# RoomModule.net
KiCad netlist of a schematic drawn in Altium Designer
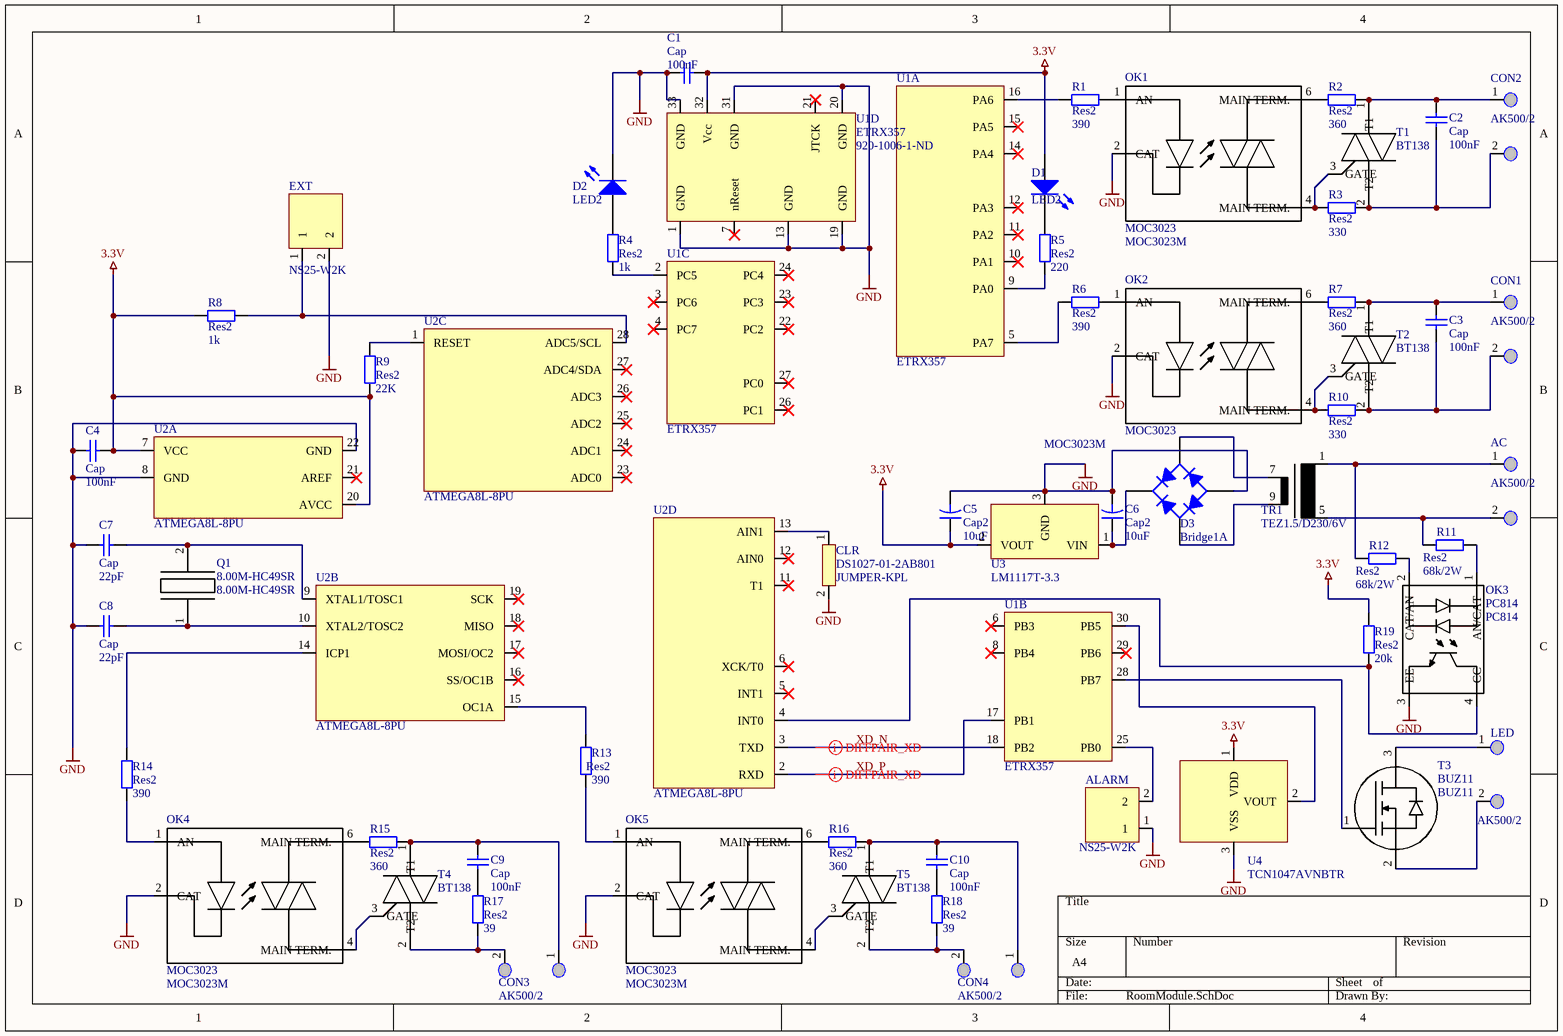
[diagram p0: RoomModule.SchDoc]

(export (version "E")
  (design (tool "Eeschema 10.0.6"))
  (components
    (comp (ref "AC")
      (value "AK500/2")
      (footprint "AK500/2")
      (description "AK500/2 connector")
      (libsource (lib "pads15l_schematic") (part "AK500/2"))
    )
    (comp (ref "ALARM")
      (value "NS25-W2K")
      (footprint "NS25-W2K")
      (description "2-pin Right Angle PCB Connector")
      (libsource (lib "pads15l_schematic") (part "NS25-W2K"))
    )
    (comp (ref "C1")
      (value "Cap")
      (footprint "RAD-0.3")
      (description "Capacitor")
      (fields (field (name "ALTIUM_VALUE") "100nF") (field (name "PUBLISHER") "Altium Limited"))
      (libsource (lib "Miscellaneous Devices") (part "Cap"))
    )
    (comp (ref "C2")
      (value "Cap")
      (footprint "RAD-0.3")
      (description "Capacitor")
      (fields (field (name "ALTIUM_VALUE") "100nF") (field (name "PUBLISHER") "Altium Limited"))
      (libsource (lib "Miscellaneous Devices") (part "Cap"))
    )
    (comp (ref "C3")
      (value "Cap")
      (footprint "RAD-0.3")
      (description "Capacitor")
      (fields (field (name "ALTIUM_VALUE") "100nF") (field (name "PUBLISHER") "Altium Limited"))
      (libsource (lib "Miscellaneous Devices") (part "Cap"))
    )
    (comp (ref "C4")
      (value "Cap")
      (footprint "RAD-0.3")
      (description "Capacitor")
      (fields (field (name "ALTIUM_VALUE") "100nF") (field (name "PUBLISHER") "Altium Limited"))
      (libsource (lib "Miscellaneous Devices") (part "Cap"))
    )
    (comp (ref "C5")
      (value "Cap2")
      (footprint "CAPR5-4X5")
      (description "Capacitor")
      (fields (field (name "ALTIUM_VALUE") "10uF") (field (name "PUBLISHER") "Altium Limited"))
      (libsource (lib "Miscellaneous Devices") (part "Cap2"))
    )
    (comp (ref "C6")
      (value "Cap2")
      (footprint "CAPR5-4X5")
      (description "Capacitor")
      (fields (field (name "ALTIUM_VALUE") "10uF") (field (name "PUBLISHER") "Altium Limited"))
      (libsource (lib "Miscellaneous Devices") (part "Cap2"))
    )
    (comp (ref "C7")
      (value "Cap")
      (footprint "RAD-0.3")
      (description "Capacitor")
      (fields (field (name "ALTIUM_VALUE") "22pF") (field (name "PUBLISHER") "Altium Limited"))
      (libsource (lib "Miscellaneous Devices") (part "Cap"))
    )
    (comp (ref "C8")
      (value "Cap")
      (footprint "RAD-0.3")
      (description "Capacitor")
      (fields (field (name "ALTIUM_VALUE") "22pF") (field (name "PUBLISHER") "Altium Limited"))
      (libsource (lib "Miscellaneous Devices") (part "Cap"))
    )
    (comp (ref "C9")
      (value "Cap")
      (footprint "RAD-0.3")
      (description "Capacitor")
      (fields (field (name "ALTIUM_VALUE") "100nF") (field (name "PUBLISHER") "Altium Limited"))
      (libsource (lib "Miscellaneous Devices") (part "Cap"))
    )
    (comp (ref "C10")
      (value "Cap")
      (footprint "RAD-0.3")
      (description "Capacitor")
      (fields (field (name "ALTIUM_VALUE") "100nF") (field (name "PUBLISHER") "Altium Limited"))
      (libsource (lib "Miscellaneous Devices") (part "Cap"))
    )
    (comp (ref "CLR")
      (value "DS1027-01-2AB801")
      (footprint "DS1027-01")
      (description "2.54 mm jumper")
      (fields (field (name "SUPPLIER PART NUMBER 1") "JUMPER-KPL"))
      (libsource (lib "pads15l_schematic") (part "DS1027-01-2AB801"))
    )
    (comp (ref "CON1")
      (value "AK500/2")
      (footprint "AK500/2")
      (description "AK500/2 connector")
      (libsource (lib "pads15l_schematic") (part "AK500/2"))
    )
    (comp (ref "CON2")
      (value "AK500/2")
      (footprint "AK500/2")
      (description "AK500/2 connector")
      (libsource (lib "pads15l_schematic") (part "AK500/2"))
    )
    (comp (ref "CON3")
      (value "AK500/2")
      (footprint "AK500/2")
      (description "AK500/2 connector")
      (libsource (lib "pads15l_schematic") (part "AK500/2"))
    )
    (comp (ref "CON4")
      (value "AK500/2")
      (footprint "AK500/2")
      (description "AK500/2 connector")
      (libsource (lib "pads15l_schematic") (part "AK500/2"))
    )
    (comp (ref "D1")
      (value "LED2")
      (footprint "3.2X1.6X1.1")
      (description "Typical RED, GREEN, YELLOW, AMBER GaAs LED")
      (fields (field (name "PUBLISHER") "Altium Limited"))
      (libsource (lib "Miscellaneous Devices") (part "LED2"))
    )
    (comp (ref "D2")
      (value "LED2")
      (footprint "3.2X1.6X1.1")
      (description "Typical RED, GREEN, YELLOW, AMBER GaAs LED")
      (fields (field (name "PUBLISHER") "Altium Limited"))
      (libsource (lib "Miscellaneous Devices") (part "LED2"))
    )
    (comp (ref "D3")
      (value "Bridge1A")
      (footprint "D-38")
      (description "Full Wave Diode Bridge")
      (fields (field (name "PUBLISHER") "Altium Limited"))
      (libsource (lib "Miscellaneous Devices") (part "Bridge1"))
    )
    (comp (ref "EXT")
      (value "NS25-W2K")
      (footprint "NS25-W2K")
      (description "2-pin Right Angle PCB Connector")
      (libsource (lib "") (part "NS25-W2K_1"))
    )
    (comp (ref "LED")
      (value "AK500/2")
      (footprint "AK500/2")
      (description "AK500/2 connector")
      (libsource (lib "pads15l_schematic") (part "AK500/2"))
    )
    (comp (ref "OK1")
      (value "MOC3023")
      (footprint "DIP6")
      (description "6-Pin DIP Random-Phase Optoisolators Triac Driver Output")
      (fields (field (name "SUPPLIER PART NUMBER 1") "MOC3023M"))
      (libsource (lib "pads15l_schematic") (part "MOC3023"))
    )
    (comp (ref "OK2")
      (value "MOC3023")
      (footprint "DIP6")
      (description "6-Pin DIP Random-Phase Optoisolators Triac Driver Output")
      (fields (field (name "SUPPLIER PART NUMBER 1") "MOC3023M"))
      (libsource (lib "pads15l_schematic") (part "MOC3023"))
    )
    (comp (ref "OK3")
      (value "PC814")
      (footprint "DIP4")
      (description "4 pin DIP phototransistor photocoupler")
      (fields (field (name "SUPPLIER PART NUMBER 1") "PC814"))
      (libsource (lib "pads15l_schematic") (part "PC814"))
    )
    (comp (ref "OK4")
      (value "MOC3023")
      (footprint "DIP6")
      (description "6-Pin DIP Random-Phase Optoisolators Triac Driver Output")
      (fields (field (name "SUPPLIER PART NUMBER 1") "MOC3023M"))
      (libsource (lib "pads15l_schematic") (part "MOC3023"))
    )
    (comp (ref "OK5")
      (value "MOC3023")
      (footprint "DIP6")
      (description "6-Pin DIP Random-Phase Optoisolators Triac Driver Output")
      (fields (field (name "SUPPLIER PART NUMBER 1") "MOC3023M"))
      (libsource (lib "pads15l_schematic") (part "MOC3023"))
    )
    (comp (ref "Q1")
      (value "8.00M-HC49SR")
      (footprint "HC49-S")
      (description "HC49SR 8 MHz crystal")
      (fields (field (name "SUPPLIER PART NUMBER 1") "8.00M-HC49SR"))
      (libsource (lib "pads15l_schematic") (part "8.00M-HC49SR"))
    )
    (comp (ref "R1")
      (value "Res2")
      (footprint "AXIAL-0.4")
      (description "Resistor")
      (fields (field (name "ALTIUM_VALUE") "390") (field (name "PUBLISHER") "Altium Limited"))
      (libsource (lib "") (part "Res2_1"))
    )
    (comp (ref "R2")
      (value "Res2")
      (footprint "AXIAL-0.4")
      (description "Resistor")
      (fields (field (name "ALTIUM_VALUE") "360") (field (name "PUBLISHER") "Altium Limited"))
      (libsource (lib "") (part "Res2_1"))
    )
    (comp (ref "R3")
      (value "Res2")
      (footprint "AXIAL-0.4")
      (description "Resistor")
      (fields (field (name "ALTIUM_VALUE") "330") (field (name "PUBLISHER") "Altium Limited"))
      (libsource (lib "") (part "Res2_1"))
    )
    (comp (ref "R4")
      (value "Res2")
      (footprint "AXIAL-0.4")
      (description "Resistor")
      (fields (field (name "ALTIUM_VALUE") "1k") (field (name "PUBLISHER") "Altium Limited"))
      (libsource (lib "") (part "Res2_3"))
    )
    (comp (ref "R5")
      (value "Res2")
      (footprint "AXIAL-0.4")
      (description "Resistor")
      (fields (field (name "ALTIUM_VALUE") "220") (field (name "PUBLISHER") "Altium Limited"))
      (libsource (lib "") (part "Res2_3"))
    )
    (comp (ref "R6")
      (value "Res2")
      (footprint "AXIAL-0.4")
      (description "Resistor")
      (fields (field (name "ALTIUM_VALUE") "390") (field (name "PUBLISHER") "Altium Limited"))
      (libsource (lib "") (part "Res2_1"))
    )
    (comp (ref "R7")
      (value "Res2")
      (footprint "AXIAL-0.4")
      (description "Resistor")
      (fields (field (name "ALTIUM_VALUE") "360") (field (name "PUBLISHER") "Altium Limited"))
      (libsource (lib "") (part "Res2_1"))
    )
    (comp (ref "R8")
      (value "Res2")
      (footprint "AXIAL-0.4")
      (description "Resistor")
      (fields (field (name "ALTIUM_VALUE") "1k") (field (name "PUBLISHER") "Altium Limited"))
      (libsource (lib "") (part "Res2_2"))
    )
    (comp (ref "R9")
      (value "Res2")
      (footprint "AXIAL-0.4")
      (description "Resistor")
      (fields (field (name "ALTIUM_VALUE") "22K") (field (name "PUBLISHER") "Altium Limited"))
      (libsource (lib "Miscellaneous Devices") (part "Res2"))
    )
    (comp (ref "R10")
      (value "Res2")
      (footprint "AXIAL-0.4")
      (description "Resistor")
      (fields (field (name "ALTIUM_VALUE") "330") (field (name "PUBLISHER") "Altium Limited"))
      (libsource (lib "") (part "Res2_1"))
    )
    (comp (ref "R11")
      (value "Res2")
      (footprint "AXIAL-0.4")
      (description "Resistor")
      (fields (field (name "ALTIUM_VALUE") "68k/2W") (field (name "PUBLISHER") "Altium Limited"))
      (libsource (lib "") (part "Res2_2"))
    )
    (comp (ref "R12")
      (value "Res2")
      (footprint "AXIAL-0.4")
      (description "Resistor")
      (fields (field (name "ALTIUM_VALUE") "68k/2W") (field (name "PUBLISHER") "Altium Limited"))
      (libsource (lib "") (part "Res2_2"))
    )
    (comp (ref "R13")
      (value "Res2")
      (footprint "AXIAL-0.4")
      (description "Resistor")
      (fields (field (name "ALTIUM_VALUE") "390") (field (name "PUBLISHER") "Altium Limited"))
      (libsource (lib "") (part "Res2_3"))
    )
    (comp (ref "R14")
      (value "Res2")
      (footprint "AXIAL-0.4")
      (description "Resistor")
      (fields (field (name "ALTIUM_VALUE") "390") (field (name "PUBLISHER") "Altium Limited"))
      (libsource (lib "") (part "Res2_3"))
    )
    (comp (ref "R15")
      (value "Res2")
      (footprint "AXIAL-0.4")
      (description "Resistor")
      (fields (field (name "ALTIUM_VALUE") "360") (field (name "PUBLISHER") "Altium Limited"))
      (libsource (lib "") (part "Res2_1"))
    )
    (comp (ref "R16")
      (value "Res2")
      (footprint "AXIAL-0.4")
      (description "Resistor")
      (fields (field (name "ALTIUM_VALUE") "360") (field (name "PUBLISHER") "Altium Limited"))
      (libsource (lib "") (part "Res2_1"))
    )
    (comp (ref "R17")
      (value "Res2")
      (footprint "AXIAL-0.4")
      (description "Resistor")
      (fields (field (name "ALTIUM_VALUE") "39") (field (name "PUBLISHER") "Altium Limited"))
      (libsource (lib "") (part "Res2_3"))
    )
    (comp (ref "R18")
      (value "Res2")
      (footprint "AXIAL-0.4")
      (description "Resistor")
      (fields (field (name "ALTIUM_VALUE") "39") (field (name "PUBLISHER") "Altium Limited"))
      (libsource (lib "") (part "Res2_3"))
    )
    (comp (ref "R19")
      (value "Res2")
      (footprint "AXIAL-0.4")
      (description "Resistor")
      (fields (field (name "ALTIUM_VALUE") "20k") (field (name "PUBLISHER") "Altium Limited"))
      (libsource (lib "") (part "Res2_3"))
    )
    (comp (ref "T1")
      (value "BT138")
      (footprint "TO220AB")
      (libsource (lib "pads15l_schematic") (part "BT138"))
    )
    (comp (ref "T2")
      (value "BT138")
      (footprint "TO220AB")
      (libsource (lib "pads15l_schematic") (part "BT138"))
    )
    (comp (ref "T3")
      (value "BUZ11")
      (footprint "TO220AB")
      (description "N-Channel Power MOSFET 50V, 30A, 40mOhm")
      (fields (field (name "SUPPLIER PART NUMBER 1") "BUZ11"))
      (libsource (lib "pads15l_schematic") (part "BUZ11"))
    )
    (comp (ref "T4")
      (value "BT138")
      (footprint "TO220AB")
      (libsource (lib "pads15l_schematic") (part "BT138"))
    )
    (comp (ref "T5")
      (value "BT138")
      (footprint "TO220AB")
      (libsource (lib "pads15l_schematic") (part "BT138"))
    )
    (comp (ref "TR1")
      (value "TEZ1.5/D230/6V")
      (footprint "TEZ1.5")
      (description "Transformer for PCB")
      (libsource (lib "pads15l_schematic") (part "TEZ1.5/D230/6V"))
    )
    (comp (ref "U1")
      (value "ETRX357")
      (footprint "ETRX3")
      (description "Low power 2.4GHz ZigBee module, based on the latest Ember EM357 single chip ZigBeeTM solution")
      (fields (field (name "SUPPLIER PART NUMBER 1") "920-1006-1-ND"))
      (libsource (lib "") (part "ETRX357_2"))
    )
    (comp (ref "U2")
      (value "ATMEGA8L-8PU")
      (footprint "DIP28_600")
      (description "8-bit AVR with 8K Bytes In-System Programmable Flash")
      (libsource (lib "pads15l_schematic") (part "ATMEGA8L-8PU"))
    )
    (comp (ref "U3")
      (value "LM1117T-3.3")
      (footprint "TO252")
      (description "LDO voltage regulator with 800mA output current and 3.3V fixed voltage")
      (libsource (lib "pads15l_schematic") (part "LM1117DT-3.3"))
    )
    (comp (ref "U4")
      (value "TCN1047AVNBTR")
      (footprint "SOT23B")
      (description "Precision Temperature-to-Voltage Converter")
      (libsource (lib "pads15l_schematic") (part "TC1047AVNBTR"))
    )
  )
  (nets
    (net (code "1") (name "/XD_N") (class "Default")
      (node (ref "U1") (pin "18") (pinfunction "PB2_18") (pintype "passive"))
      (node (ref "U2") (pin "3") (pinfunction "TXD_3") (pintype "passive"))
    )
    (net (code "2") (name "/XD_P") (class "Default")
      (node (ref "U1") (pin "17") (pinfunction "PB1_17") (pintype "passive"))
      (node (ref "U2") (pin "2") (pinfunction "RXD_2") (pintype "passive"))
    )
    (net (code "3") (name "3.3V") (class "Default")
      (node (ref "C1") (pin "2") (pinfunction "2_2") (pintype "passive"))
      (node (ref "C4") (pin "2") (pinfunction "2_2") (pintype "passive"))
      (node (ref "C5") (pin "1") (pinfunction "1_1") (pintype "passive"))
      (node (ref "D1") (pin "1") (pinfunction "A_1") (pintype "passive"))
      (node (ref "R19") (pin "1") (pinfunction "1_1") (pintype "passive"))
      (node (ref "R8") (pin "2") (pinfunction "2_2") (pintype "passive"))
      (node (ref "R9") (pin "1") (pinfunction "1_1") (pintype "passive"))
      (node (ref "U1") (pin "32") (pinfunction "Vcc_32") (pintype "passive"))
      (node (ref "U2") (pin "20") (pinfunction "AVCC_20") (pintype "passive"))
      (node (ref "U2") (pin "7") (pinfunction "VCC_7") (pintype "passive"))
      (node (ref "U3") (pin "2") (pinfunction "VOUT_2") (pintype "passive"))
      (node (ref "U4") (pin "1") (pinfunction "VDD_1") (pintype "passive"))
    )
    (net (code "4") (name "GND") (class "Default")
      (node (ref "ALARM") (pin "1") (pinfunction "1_1") (pintype "passive"))
      (node (ref "C1") (pin "1") (pinfunction "1_1") (pintype "passive"))
      (node (ref "C4") (pin "1") (pinfunction "1_1") (pintype "passive"))
      (node (ref "C5") (pin "2") (pinfunction "2_2") (pintype "passive"))
      (node (ref "C6") (pin "2") (pinfunction "2_2") (pintype "passive"))
      (node (ref "C7") (pin "1") (pinfunction "1_1") (pintype "passive"))
      (node (ref "C8") (pin "1") (pinfunction "1_1") (pintype "passive"))
      (node (ref "CLR") (pin "2") (pintype "passive"))
      (node (ref "D2") (pin "2") (pinfunction "K_2") (pintype "passive"))
      (node (ref "D3") (pin "3") (pinfunction "A_3") (pintype "passive"))
      (node (ref "EXT") (pin "2") (pinfunction "2_2") (pintype "passive"))
      (node (ref "OK1") (pin "2") (pinfunction "CAT_2") (pintype "passive"))
      (node (ref "OK2") (pin "2") (pinfunction "CAT_2") (pintype "passive"))
      (node (ref "OK3") (pin "3") (pinfunction "EE_3") (pintype "passive"))
      (node (ref "OK4") (pin "2") (pinfunction "CAT_2") (pintype "passive"))
      (node (ref "OK5") (pin "2") (pinfunction "CAT_2") (pintype "passive"))
      (node (ref "U1") (pin "1") (pinfunction "GND_1") (pintype "passive"))
      (node (ref "U1") (pin "13") (pinfunction "GND_13") (pintype "passive"))
      (node (ref "U1") (pin "19") (pinfunction "GND_19") (pintype "passive"))
      (node (ref "U1") (pin "20") (pinfunction "GND_20") (pintype "passive"))
      (node (ref "U1") (pin "31") (pinfunction "GND_31") (pintype "passive"))
      (node (ref "U1") (pin "33") (pinfunction "GND_33") (pintype "passive"))
      (node (ref "U2") (pin "22") (pinfunction "GND_22") (pintype "passive"))
      (node (ref "U2") (pin "8") (pinfunction "GND_8") (pintype "passive"))
      (node (ref "U3") (pin "3") (pinfunction "GND_3") (pintype "passive"))
      (node (ref "U4") (pin "3") (pinfunction "VSS_3") (pintype "passive"))
    )
    (net (code "5") (name "Net-(AC-Pad1)") (class "Default")
      (node (ref "AC") (pin "1") (pintype "passive"))
      (node (ref "R12") (pin "2") (pinfunction "2_2") (pintype "passive"))
      (node (ref "TR1") (pin "1") (pintype "passive"))
    )
    (net (code "6") (name "Net-(AC-Pad2)") (class "Default")
      (node (ref "AC") (pin "2") (pintype "passive"))
      (node (ref "R11") (pin "2") (pinfunction "2_2") (pintype "passive"))
      (node (ref "TR1") (pin "5") (pintype "passive"))
    )
    (net (code "7") (name "Net-(C9-Pad1)") (class "Default")
      (node (ref "C9") (pin "1") (pinfunction "1_1") (pintype "passive"))
      (node (ref "R17") (pin "1") (pinfunction "1_1") (pintype "passive"))
    )
    (net (code "8") (name "Net-(C10-Pad1)") (class "Default")
      (node (ref "C10") (pin "1") (pinfunction "1_1") (pintype "passive"))
      (node (ref "R18") (pin "1") (pinfunction "1_1") (pintype "passive"))
    )
    (net (code "9") (name "Net-(D1-K)") (class "Default")
      (node (ref "D1") (pin "2") (pinfunction "K_2") (pintype "passive"))
      (node (ref "R5") (pin "1") (pinfunction "1_1") (pintype "passive"))
    )
    (net (code "10") (name "Net-(D2-A)") (class "Default")
      (node (ref "D2") (pin "1") (pinfunction "A_1") (pintype "passive"))
      (node (ref "R4") (pin "1") (pinfunction "1_1") (pintype "passive"))
    )
    (net (code "11") (name "Net-(D3-C-Pad2)") (class "Default")
      (node (ref "D3") (pin "2") (pinfunction "C_2") (pintype "passive"))
      (node (ref "TR1") (pin "7") (pintype "passive"))
    )
    (net (code "12") (name "Net-(D3-C-Pad4)") (class "Default")
      (node (ref "D3") (pin "4") (pinfunction "C_4") (pintype "passive"))
      (node (ref "TR1") (pin "9") (pintype "passive"))
    )
    (net (code "13") (name "Net-(D3-K)") (class "Default")
      (node (ref "C6") (pin "1") (pinfunction "1_1") (pintype "passive"))
      (node (ref "D3") (pin "1") (pinfunction "K_1") (pintype "passive"))
      (node (ref "U3") (pin "1") (pinfunction "VIN_1") (pintype "passive"))
    )
    (net (code "14") (name "Net-(LED-Pad1)") (class "Default")
      (node (ref "LED") (pin "1") (pintype "passive"))
      (node (ref "T3") (pin "3") (pintype "passive"))
    )
    (net (code "15") (name "Net-(LED-Pad2)") (class "Default")
      (node (ref "LED") (pin "2") (pintype "passive"))
      (node (ref "T3") (pin "2") (pintype "passive"))
    )
    (net (code "16") (name "Net-(OK1-AN)") (class "Default")
      (node (ref "OK1") (pin "1") (pinfunction "AN_1") (pintype "passive"))
      (node (ref "R1") (pin "2") (pinfunction "2_2") (pintype "passive"))
    )
    (net (code "17") (name "Net-(OK1-MAIN_TERM.-Pad6)") (class "Default")
      (node (ref "OK1") (pin "6") (pinfunction "MAIN_TERM._6") (pintype "passive"))
      (node (ref "R2") (pin "1") (pinfunction "1_1") (pintype "passive"))
    )
    (net (code "18") (name "Net-(OK2-AN)") (class "Default")
      (node (ref "OK2") (pin "1") (pinfunction "AN_1") (pintype "passive"))
      (node (ref "R6") (pin "2") (pinfunction "2_2") (pintype "passive"))
    )
    (net (code "19") (name "Net-(OK2-MAIN_TERM.-Pad6)") (class "Default")
      (node (ref "OK2") (pin "6") (pinfunction "MAIN_TERM._6") (pintype "passive"))
      (node (ref "R7") (pin "1") (pinfunction "1_1") (pintype "passive"))
    )
    (net (code "20") (name "Net-(OK3-AN{slash}CAT)") (class "Default")
      (node (ref "OK3") (pin "1") (pinfunction "AN/CAT_1") (pintype "passive"))
      (node (ref "R11") (pin "1") (pinfunction "1_1") (pintype "passive"))
    )
    (net (code "21") (name "Net-(OK3-CAT{slash}AN)") (class "Default")
      (node (ref "OK3") (pin "2") (pinfunction "CAT/AN_2") (pintype "passive"))
      (node (ref "R12") (pin "1") (pinfunction "1_1") (pintype "passive"))
    )
    (net (code "22") (name "Net-(OK3-CC)") (class "Default")
      (node (ref "OK3") (pin "4") (pinfunction "CC_4") (pintype "passive"))
      (node (ref "R19") (pin "2") (pinfunction "2_2") (pintype "passive"))
      (node (ref "U2") (pin "4") (pinfunction "INT0_4") (pintype "passive"))
    )
    (net (code "23") (name "Net-(OK4-AN)") (class "Default")
      (node (ref "OK4") (pin "1") (pinfunction "AN_1") (pintype "passive"))
      (node (ref "R14") (pin "2") (pinfunction "2_2") (pintype "passive"))
    )
    (net (code "24") (name "Net-(OK4-MAIN_TERM.-Pad6)") (class "Default")
      (node (ref "OK4") (pin "6") (pinfunction "MAIN_TERM._6") (pintype "passive"))
      (node (ref "R15") (pin "1") (pinfunction "1_1") (pintype "passive"))
    )
    (net (code "25") (name "Net-(OK5-AN)") (class "Default")
      (node (ref "OK5") (pin "1") (pinfunction "AN_1") (pintype "passive"))
      (node (ref "R13") (pin "2") (pinfunction "2_2") (pintype "passive"))
    )
    (net (code "26") (name "Net-(OK5-MAIN_TERM.-Pad6)") (class "Default")
      (node (ref "OK5") (pin "6") (pinfunction "MAIN_TERM._6") (pintype "passive"))
      (node (ref "R16") (pin "1") (pinfunction "1_1") (pintype "passive"))
    )
    (net (code "27") (name "Net-(T1-GATE)") (class "Default")
      (node (ref "OK1") (pin "4") (pinfunction "MAIN_TERM._4") (pintype "passive"))
      (node (ref "R3") (pin "1") (pinfunction "1_1") (pintype "passive"))
      (node (ref "T1") (pin "3") (pinfunction "GATE_3") (pintype "passive"))
    )
    (net (code "28") (name "Net-(T1-T1)") (class "Default")
      (node (ref "C2") (pin "2") (pinfunction "2_2") (pintype "passive"))
      (node (ref "CON2") (pin "1") (pintype "passive"))
      (node (ref "R2") (pin "2") (pinfunction "2_2") (pintype "passive"))
      (node (ref "T1") (pin "1") (pinfunction "T1_1") (pintype "passive"))
    )
    (net (code "29") (name "Net-(T1-T2)") (class "Default")
      (node (ref "C2") (pin "1") (pinfunction "1_1") (pintype "passive"))
      (node (ref "CON2") (pin "2") (pintype "passive"))
      (node (ref "R3") (pin "2") (pinfunction "2_2") (pintype "passive"))
      (node (ref "T1") (pin "2") (pinfunction "T2_2") (pintype "passive"))
    )
    (net (code "30") (name "Net-(T2-GATE)") (class "Default")
      (node (ref "OK2") (pin "4") (pinfunction "MAIN_TERM._4") (pintype "passive"))
      (node (ref "R10") (pin "1") (pinfunction "1_1") (pintype "passive"))
      (node (ref "T2") (pin "3") (pinfunction "GATE_3") (pintype "passive"))
    )
    (net (code "31") (name "Net-(T2-T1)") (class "Default")
      (node (ref "C3") (pin "2") (pinfunction "2_2") (pintype "passive"))
      (node (ref "CON1") (pin "1") (pintype "passive"))
      (node (ref "R7") (pin "2") (pinfunction "2_2") (pintype "passive"))
      (node (ref "T2") (pin "1") (pinfunction "T1_1") (pintype "passive"))
    )
    (net (code "32") (name "Net-(T2-T2)") (class "Default")
      (node (ref "C3") (pin "1") (pinfunction "1_1") (pintype "passive"))
      (node (ref "CON1") (pin "2") (pintype "passive"))
      (node (ref "R10") (pin "2") (pinfunction "2_2") (pintype "passive"))
      (node (ref "T2") (pin "2") (pinfunction "T2_2") (pintype "passive"))
    )
    (net (code "33") (name "Net-(T4-GATE)") (class "Default")
      (node (ref "OK4") (pin "4") (pinfunction "MAIN_TERM._4") (pintype "passive"))
      (node (ref "T4") (pin "3") (pinfunction "GATE_3") (pintype "passive"))
    )
    (net (code "34") (name "Net-(T4-T1)") (class "Default")
      (node (ref "C9") (pin "2") (pinfunction "2_2") (pintype "passive"))
      (node (ref "CON3") (pin "1") (pintype "passive"))
      (node (ref "R15") (pin "2") (pinfunction "2_2") (pintype "passive"))
      (node (ref "T4") (pin "1") (pinfunction "T1_1") (pintype "passive"))
    )
    (net (code "35") (name "Net-(T4-T2)") (class "Default")
      (node (ref "CON3") (pin "2") (pintype "passive"))
      (node (ref "R17") (pin "2") (pinfunction "2_2") (pintype "passive"))
      (node (ref "T4") (pin "2") (pinfunction "T2_2") (pintype "passive"))
    )
    (net (code "36") (name "Net-(T5-GATE)") (class "Default")
      (node (ref "OK5") (pin "4") (pinfunction "MAIN_TERM._4") (pintype "passive"))
      (node (ref "T5") (pin "3") (pinfunction "GATE_3") (pintype "passive"))
    )
    (net (code "37") (name "Net-(T5-T1)") (class "Default")
      (node (ref "C10") (pin "2") (pinfunction "2_2") (pintype "passive"))
      (node (ref "CON4") (pin "1") (pintype "passive"))
      (node (ref "R16") (pin "2") (pinfunction "2_2") (pintype "passive"))
      (node (ref "T5") (pin "1") (pinfunction "T1_1") (pintype "passive"))
    )
    (net (code "38") (name "Net-(T5-T2)") (class "Default")
      (node (ref "CON4") (pin "2") (pintype "passive"))
      (node (ref "R18") (pin "2") (pinfunction "2_2") (pintype "passive"))
      (node (ref "T5") (pin "2") (pinfunction "T2_2") (pintype "passive"))
    )
    (net (code "39") (name "Net-(U1A-PA0)") (class "Default")
      (node (ref "R5") (pin "2") (pinfunction "2_2") (pintype "passive"))
      (node (ref "U1") (pin "9") (pinfunction "PA0_9") (pintype "passive"))
    )
    (net (code "40") (name "Net-(U1A-PA6)") (class "Default")
      (node (ref "R1") (pin "1") (pinfunction "1_1") (pintype "passive"))
      (node (ref "U1") (pin "16") (pinfunction "PA6_16") (pintype "passive"))
    )
    (net (code "41") (name "Net-(U1A-PA7)") (class "Default")
      (node (ref "R6") (pin "1") (pinfunction "1_1") (pintype "passive"))
      (node (ref "U1") (pin "5") (pinfunction "PA7_5") (pintype "passive"))
    )
    (net (code "42") (name "Net-(U1B-PB0)") (class "Default")
      (node (ref "ALARM") (pin "2") (pinfunction "2_2") (pintype "passive"))
      (node (ref "U1") (pin "25") (pinfunction "PB0_25") (pintype "passive"))
    )
    (net (code "43") (name "Net-(U1B-PB5)") (class "Default")
      (node (ref "U1") (pin "30") (pinfunction "PB5_30") (pintype "passive"))
      (node (ref "U4") (pin "2") (pinfunction "VOUT_2") (pintype "passive"))
    )
    (net (code "44") (name "Net-(U1B-PB7)") (class "Default")
      (node (ref "T3") (pin "1") (pintype "passive"))
      (node (ref "U1") (pin "28") (pinfunction "PB7_28") (pintype "passive"))
    )
    (net (code "45") (name "Net-(U1C-PC5)") (class "Default")
      (node (ref "R4") (pin "2") (pinfunction "2_2") (pintype "passive"))
      (node (ref "U1") (pin "2") (pinfunction "PC5_2") (pintype "passive"))
    )
    (net (code "46") (name "Net-(U2B-ICP1)") (class "Default")
      (node (ref "R14") (pin "1") (pinfunction "1_1") (pintype "passive"))
      (node (ref "U2") (pin "14") (pinfunction "ICP1_14") (pintype "passive"))
    )
    (net (code "47") (name "Net-(U2B-OC1A)") (class "Default")
      (node (ref "R13") (pin "1") (pinfunction "1_1") (pintype "passive"))
      (node (ref "U2") (pin "15") (pinfunction "OC1A_15") (pintype "passive"))
    )
    (net (code "48") (name "Net-(U2B-XTAL1{slash}TOSC1)") (class "Default")
      (node (ref "C7") (pin "2") (pinfunction "2_2") (pintype "passive"))
      (node (ref "Q1") (pin "2") (pintype "passive"))
      (node (ref "U2") (pin "9") (pinfunction "XTAL1/TOSC1_9") (pintype "passive"))
    )
    (net (code "49") (name "Net-(U2B-XTAL2{slash}TOSC2)") (class "Default")
      (node (ref "C8") (pin "2") (pinfunction "2_2") (pintype "passive"))
      (node (ref "Q1") (pin "1") (pintype "passive"))
      (node (ref "U2") (pin "10") (pinfunction "XTAL2/TOSC2_10") (pintype "passive"))
    )
    (net (code "50") (name "Net-(U2C-ADC5{slash}SCL)") (class "Default")
      (node (ref "EXT") (pin "1") (pinfunction "1_1") (pintype "passive"))
      (node (ref "R8") (pin "1") (pinfunction "1_1") (pintype "passive"))
      (node (ref "U2") (pin "28") (pinfunction "ADC5/SCL_28") (pintype "passive"))
    )
    (net (code "51") (name "Net-(U2C-RESET)") (class "Default")
      (node (ref "R9") (pin "2") (pinfunction "2_2") (pintype "passive"))
      (node (ref "U2") (pin "1") (pinfunction "RESET_1") (pintype "passive"))
    )
    (net (code "52") (name "Net-(U2D-AIN1)") (class "Default")
      (node (ref "CLR") (pin "1") (pintype "passive"))
      (node (ref "U2") (pin "13") (pinfunction "AIN1_13") (pintype "passive"))
    )
    (net (code "53") (name "unconnected-(U1A-PA1-Pad10)") (class "Default")
      (node (ref "U1") (pin "10") (pinfunction "PA1_10") (pintype "passive+no_connect"))
    )
    (net (code "54") (name "unconnected-(U1A-PA2-Pad11)") (class "Default")
      (node (ref "U1") (pin "11") (pinfunction "PA2_11") (pintype "passive+no_connect"))
    )
    (net (code "55") (name "unconnected-(U1A-PA3-Pad12)") (class "Default")
      (node (ref "U1") (pin "12") (pinfunction "PA3_12") (pintype "passive+no_connect"))
    )
    (net (code "56") (name "unconnected-(U1A-PA4-Pad14)") (class "Default")
      (node (ref "U1") (pin "14") (pinfunction "PA4_14") (pintype "passive+no_connect"))
    )
    (net (code "57") (name "unconnected-(U1A-PA5-Pad15)") (class "Default")
      (node (ref "U1") (pin "15") (pinfunction "PA5_15") (pintype "passive+no_connect"))
    )
    (net (code "58") (name "unconnected-(U1B-PB3-Pad6)") (class "Default")
      (node (ref "U1") (pin "6") (pinfunction "PB3_6") (pintype "passive+no_connect"))
    )
    (net (code "59") (name "unconnected-(U1B-PB4-Pad8)") (class "Default")
      (node (ref "U1") (pin "8") (pinfunction "PB4_8") (pintype "passive+no_connect"))
    )
    (net (code "60") (name "unconnected-(U1B-PB6-Pad29)") (class "Default")
      (node (ref "U1") (pin "29") (pinfunction "PB6_29") (pintype "passive+no_connect"))
    )
    (net (code "61") (name "unconnected-(U1C-PC0-Pad27)") (class "Default")
      (node (ref "U1") (pin "27") (pinfunction "PC0_27") (pintype "passive+no_connect"))
    )
    (net (code "62") (name "unconnected-(U1C-PC1-Pad26)") (class "Default")
      (node (ref "U1") (pin "26") (pinfunction "PC1_26") (pintype "passive+no_connect"))
    )
    (net (code "63") (name "unconnected-(U1C-PC2-Pad22)") (class "Default")
      (node (ref "U1") (pin "22") (pinfunction "PC2_22") (pintype "passive+no_connect"))
    )
    (net (code "64") (name "unconnected-(U1C-PC3-Pad23)") (class "Default")
      (node (ref "U1") (pin "23") (pinfunction "PC3_23") (pintype "passive+no_connect"))
    )
    (net (code "65") (name "unconnected-(U1C-PC4-Pad24)") (class "Default")
      (node (ref "U1") (pin "24") (pinfunction "PC4_24") (pintype "passive+no_connect"))
    )
    (net (code "66") (name "unconnected-(U1C-PC6-Pad3)") (class "Default")
      (node (ref "U1") (pin "3") (pinfunction "PC6_3") (pintype "passive+no_connect"))
    )
    (net (code "67") (name "unconnected-(U1C-PC7-Pad4)") (class "Default")
      (node (ref "U1") (pin "4") (pinfunction "PC7_4") (pintype "passive+no_connect"))
    )
    (net (code "68") (name "unconnected-(U1D-JTCK-Pad21)") (class "Default")
      (node (ref "U1") (pin "21") (pinfunction "JTCK_21") (pintype "passive+no_connect"))
    )
    (net (code "69") (name "unconnected-(U1D-nReset-Pad7)") (class "Default")
      (node (ref "U1") (pin "7") (pinfunction "nReset_7") (pintype "passive+no_connect"))
    )
    (net (code "70") (name "unconnected-(U2A-AREF-Pad21)") (class "Default")
      (node (ref "U2") (pin "21") (pinfunction "AREF_21") (pintype "passive+no_connect"))
    )
    (net (code "71") (name "unconnected-(U2B-MISO-Pad18)") (class "Default")
      (node (ref "U2") (pin "18") (pinfunction "MISO_18") (pintype "passive+no_connect"))
    )
    (net (code "72") (name "unconnected-(U2B-MOSI{slash}OC2-Pad17)") (class "Default")
      (node (ref "U2") (pin "17") (pinfunction "MOSI/OC2_17") (pintype "passive+no_connect"))
    )
    (net (code "73") (name "unconnected-(U2B-SCK-Pad19)") (class "Default")
      (node (ref "U2") (pin "19") (pinfunction "SCK_19") (pintype "passive+no_connect"))
    )
    (net (code "74") (name "unconnected-(U2B-SS{slash}OC1B-Pad16)") (class "Default")
      (node (ref "U2") (pin "16") (pinfunction "SS/OC1B_16") (pintype "passive+no_connect"))
    )
    (net (code "75") (name "unconnected-(U2C-ADC0-Pad23)") (class "Default")
      (node (ref "U2") (pin "23") (pinfunction "ADC0_23") (pintype "passive+no_connect"))
    )
    (net (code "76") (name "unconnected-(U2C-ADC1-Pad24)") (class "Default")
      (node (ref "U2") (pin "24") (pinfunction "ADC1_24") (pintype "passive+no_connect"))
    )
    (net (code "77") (name "unconnected-(U2C-ADC2-Pad25)") (class "Default")
      (node (ref "U2") (pin "25") (pinfunction "ADC2_25") (pintype "passive+no_connect"))
    )
    (net (code "78") (name "unconnected-(U2C-ADC3-Pad26)") (class "Default")
      (node (ref "U2") (pin "26") (pinfunction "ADC3_26") (pintype "passive+no_connect"))
    )
    (net (code "79") (name "unconnected-(U2C-ADC4{slash}SDA-Pad27)") (class "Default")
      (node (ref "U2") (pin "27") (pinfunction "ADC4/SDA_27") (pintype "passive+no_connect"))
    )
    (net (code "80") (name "unconnected-(U2D-AIN0-Pad12)") (class "Default")
      (node (ref "U2") (pin "12") (pinfunction "AIN0_12") (pintype "passive+no_connect"))
    )
    (net (code "81") (name "unconnected-(U2D-INT1-Pad5)") (class "Default")
      (node (ref "U2") (pin "5") (pinfunction "INT1_5") (pintype "passive+no_connect"))
    )
    (net (code "82") (name "unconnected-(U2D-T1-Pad11)") (class "Default")
      (node (ref "U2") (pin "11") (pinfunction "T1_11") (pintype "passive+no_connect"))
    )
    (net (code "83") (name "unconnected-(U2D-XCK{slash}T0-Pad6)") (class "Default")
      (node (ref "U2") (pin "6") (pinfunction "XCK/T0_6") (pintype "passive+no_connect"))
    )
  )
)
